# Display.net
KiCad netlist of a schematic drawn in Altium Designer
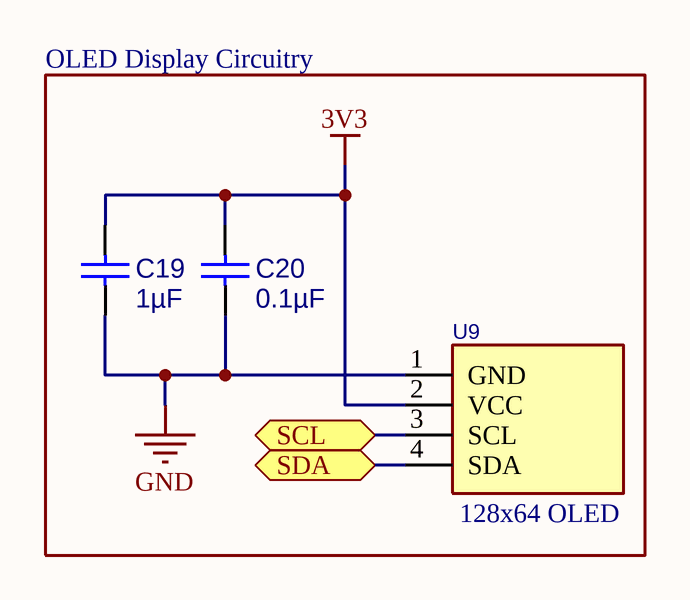
[diagram p0: Display.SchDoc]

(export (version "E")
  (design (tool "Eeschema 10.0.6"))
  (components
    (comp (ref "C19")
      (value "1µF")
      (footprint "WCAP-CSGP_0603_L1.6W0.8H0.8_Reflow")
      (description "10V tolerance")
      (libsource (lib "Altium Content Vault") (part "Capacitor_Non-Polarized"))
    )
    (comp (ref "C20")
      (value "0.1µF")
      (footprint "WCAP-CSGP_0603_L1.6W0.8H0.8_Reflow")
      (description "10V tolerance")
      (libsource (lib "Altium Content Vault") (part "Capacitor_Non-Polarized"))
    )
    (comp (ref "U9")
      (value "128x64 OLED")
      (footprint "Amazon OLED Display Module")
      (description "Hosyond 5 Pcs 0.96 Inch OLED I2C Display Module 128x64 Pixel OLED Display")
      (libsource (lib "RIT-EVT-Vault") (part "Amazon OLED Display Module"))
    )
  )
  (nets
    (net (code "1") (name "/SCL") (class "Default")
      (node (ref "U9") (pin "3") (pinfunction "SCL_3") (pintype "passive"))
    )
    (net (code "2") (name "/SDA") (class "Default")
      (node (ref "U9") (pin "4") (pinfunction "SDA_4") (pintype "passive"))
    )
    (net (code "3") (name "3V3") (class "Default")
      (node (ref "C19") (pin "2") (pinfunction "2_2") (pintype "passive"))
      (node (ref "C20") (pin "2") (pinfunction "2_2") (pintype "passive"))
      (node (ref "U9") (pin "2") (pinfunction "VCC_2") (pintype "passive"))
    )
    (net (code "4") (name "GND") (class "Default")
      (node (ref "C19") (pin "1") (pinfunction "1_1") (pintype "passive"))
      (node (ref "C20") (pin "1") (pinfunction "1_1") (pintype "passive"))
      (node (ref "U9") (pin "1") (pinfunction "GND_1") (pintype "passive"))
    )
  )
)
